# mega-breakout-v1.net
KiCad netlist of a schematic drawn in EAGLE
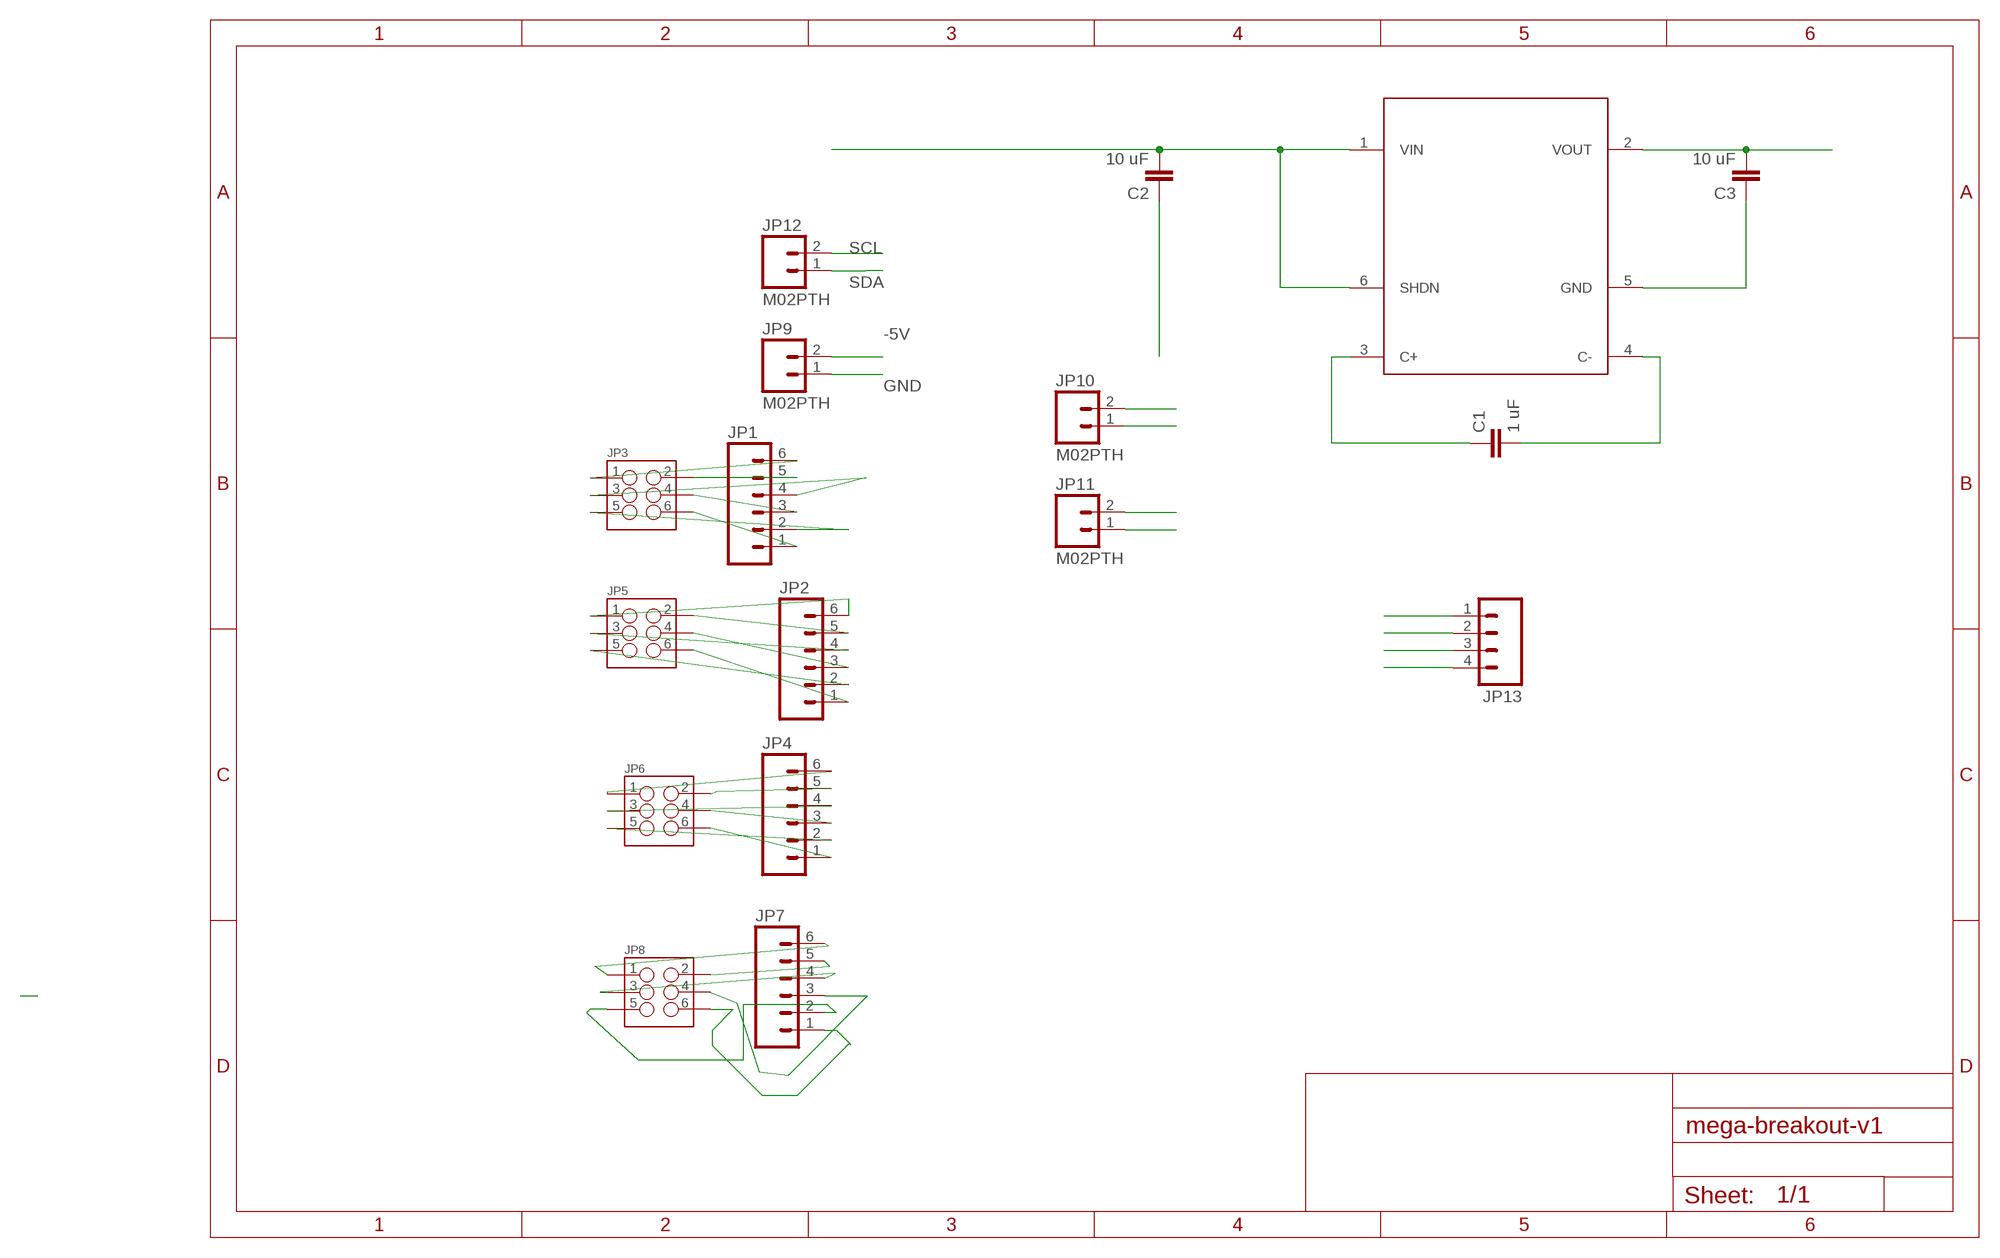
[diagram p0: schematic, sheet 1]

(export (version "E")
  (design (tool "Eeschema 10.0.6"))
  (components
    (comp (ref "C1")
      (value "1 uF")
      (footprint "eagle-import:0805")
      (libsource (lib "eagle-import") (part "CAP0805"))
    )
    (comp (ref "C2")
      (value "10 uF")
      (footprint "eagle-import:0805")
      (libsource (lib "eagle-import") (part "CAP0805"))
    )
    (comp (ref "C3")
      (value "10 uF")
      (footprint "eagle-import:0805")
      (libsource (lib "eagle-import") (part "CAP0805"))
    )
    (comp (ref "JP1")
      (value "M06NO_SILK")
      (footprint "eagle-import:1X06_NO_SILK")
      (libsource (lib "eagle-import") (part "M06NO_SILK"))
    )
    (comp (ref "JP2")
      (value "M06NO_SILK")
      (footprint "eagle-import:1X06_NO_SILK")
      (libsource (lib "eagle-import") (part "M06NO_SILK"))
    )
    (comp (ref "JP3")
      (value "M03X22X3_SILK_SM")
      (footprint "eagle-import:2X3")
      (libsource (lib "eagle-import") (part "M03X22X3_SILK_SM"))
    )
    (comp (ref "JP4")
      (value "M06NO_SILK")
      (footprint "eagle-import:1X06_NO_SILK")
      (libsource (lib "eagle-import") (part "M06NO_SILK"))
    )
    (comp (ref "JP5")
      (value "M03X22X3_SILK_SM")
      (footprint "eagle-import:2X3")
      (libsource (lib "eagle-import") (part "M03X22X3_SILK_SM"))
    )
    (comp (ref "JP6")
      (value "M03X22X3_SILK_SM")
      (footprint "eagle-import:2X3")
      (libsource (lib "eagle-import") (part "M03X22X3_SILK_SM"))
    )
    (comp (ref "JP7")
      (value "M06NO_SILK")
      (footprint "eagle-import:1X06_NO_SILK")
      (libsource (lib "eagle-import") (part "M06NO_SILK"))
    )
    (comp (ref "JP8")
      (value "M03X22X3_SILK_SM")
      (footprint "eagle-import:2X3")
      (libsource (lib "eagle-import") (part "M03X22X3_SILK_SM"))
    )
    (comp (ref "JP9")
      (value "M02PTH")
      (footprint "eagle-import:1X02")
      (libsource (lib "eagle-import") (part "M02PTH"))
    )
    (comp (ref "JP10")
      (value "M02PTH")
      (footprint "eagle-import:1X02")
      (libsource (lib "eagle-import") (part "M02PTH"))
    )
    (comp (ref "JP11")
      (value "M02PTH")
      (footprint "eagle-import:1X02")
      (libsource (lib "eagle-import") (part "M02PTH"))
    )
    (comp (ref "JP12")
      (value "M02PTH")
      (footprint "eagle-import:1X02")
      (libsource (lib "eagle-import") (part "M02PTH"))
    )
    (comp (ref "JP13")
      (value "M04PTH")
      (footprint "eagle-import:1X04")
      (libsource (lib "eagle-import") (part "M04PTH"))
    )
    (comp (ref "U1")
      (value "LTC1983")
      (footprint "eagle-import:SSOT23-6")
      (libsource (lib "eagle-import") (part "LTC1983"))
    )
  )
  (nets
    (net (code "1") (name "/-5V") (class "Default")
      (node (ref "C3") (pin "2") (pinfunction "2_2") (pintype "passive"))
      (node (ref "JP9") (pin "2") (pinfunction "2_2") (pintype "passive"))
      (node (ref "U1") (pin "2") (pinfunction "VOUT_2") (pintype "bidirectional"))
    )
    (net (code "2") (name "/GND") (class "Default")
      (node (ref "JP13") (pin "3") (pinfunction "3_3") (pintype "passive"))
      (node (ref "JP9") (pin "1") (pinfunction "1_1") (pintype "passive"))
    )
    (net (code "3") (name "/SCL") (class "Default")
      (node (ref "JP12") (pin "2") (pinfunction "2_2") (pintype "passive"))
      (node (ref "JP13") (pin "2") (pinfunction "2_2") (pintype "passive"))
    )
    (net (code "4") (name "/SDA") (class "Default")
      (node (ref "JP12") (pin "1") (pinfunction "1_1") (pintype "passive"))
      (node (ref "JP13") (pin "1") (pinfunction "1_1") (pintype "passive"))
    )
    (net (code "5") (name "/VCC") (class "Default")
      (node (ref "C2") (pin "2") (pinfunction "2_2") (pintype "passive"))
      (node (ref "JP11") (pin "1") (pinfunction "1_1") (pintype "passive"))
      (node (ref "JP11") (pin "2") (pinfunction "2_2") (pintype "passive"))
      (node (ref "JP13") (pin "4") (pinfunction "4_4") (pintype "passive"))
      (node (ref "U1") (pin "1") (pinfunction "VIN_1") (pintype "bidirectional"))
      (node (ref "U1") (pin "6") (pinfunction "SHDN_6") (pintype "bidirectional"))
    )
    (net (code "6") (name "/VCC1") (class "Default")
      (node (ref "C2") (pin "1") (pinfunction "1_1") (pintype "passive"))
      (node (ref "C3") (pin "1") (pinfunction "1_1") (pintype "passive"))
      (node (ref "U1") (pin "5") (pinfunction "GND_5") (pintype "bidirectional"))
    )
    (net (code "7") (name "Net-(JP1-Pad1)") (class "Default")
      (node (ref "JP1") (pin "1") (pinfunction "1_1") (pintype "passive"))
      (node (ref "JP3") (pin "6") (pinfunction "6_6") (pintype "bidirectional"))
    )
    (net (code "8") (name "Net-(JP1-Pad2)") (class "Default")
      (node (ref "JP1") (pin "2") (pinfunction "2_2") (pintype "passive"))
      (node (ref "JP3") (pin "5") (pinfunction "5_5") (pintype "bidirectional"))
    )
    (net (code "9") (name "Net-(JP1-Pad3)") (class "Default")
      (node (ref "JP1") (pin "3") (pinfunction "3_3") (pintype "passive"))
      (node (ref "JP3") (pin "4") (pinfunction "4_4") (pintype "bidirectional"))
    )
    (net (code "10") (name "Net-(JP1-Pad4)") (class "Default")
      (node (ref "JP1") (pin "4") (pinfunction "4_4") (pintype "passive"))
      (node (ref "JP3") (pin "3") (pinfunction "3_3") (pintype "bidirectional"))
    )
    (net (code "11") (name "Net-(JP1-Pad5)") (class "Default")
      (node (ref "JP1") (pin "5") (pinfunction "5_5") (pintype "passive"))
      (node (ref "JP3") (pin "2") (pinfunction "2_2") (pintype "bidirectional"))
    )
    (net (code "12") (name "Net-(JP1-Pad6)") (class "Default")
      (node (ref "JP1") (pin "6") (pinfunction "6_6") (pintype "passive"))
      (node (ref "JP3") (pin "1") (pinfunction "1_1") (pintype "bidirectional"))
    )
    (net (code "13") (name "Net-(JP2-Pad1)") (class "Default")
      (node (ref "JP2") (pin "1") (pinfunction "1_1") (pintype "passive"))
      (node (ref "JP5") (pin "6") (pinfunction "6_6") (pintype "bidirectional"))
    )
    (net (code "14") (name "Net-(JP2-Pad2)") (class "Default")
      (node (ref "JP2") (pin "2") (pinfunction "2_2") (pintype "passive"))
      (node (ref "JP5") (pin "5") (pinfunction "5_5") (pintype "bidirectional"))
    )
    (net (code "15") (name "Net-(JP2-Pad3)") (class "Default")
      (node (ref "JP2") (pin "3") (pinfunction "3_3") (pintype "passive"))
      (node (ref "JP5") (pin "4") (pinfunction "4_4") (pintype "bidirectional"))
    )
    (net (code "16") (name "Net-(JP2-Pad4)") (class "Default")
      (node (ref "JP2") (pin "4") (pinfunction "4_4") (pintype "passive"))
      (node (ref "JP5") (pin "3") (pinfunction "3_3") (pintype "bidirectional"))
    )
    (net (code "17") (name "Net-(JP2-Pad5)") (class "Default")
      (node (ref "JP2") (pin "5") (pinfunction "5_5") (pintype "passive"))
      (node (ref "JP5") (pin "2") (pinfunction "2_2") (pintype "bidirectional"))
    )
    (net (code "18") (name "Net-(JP2-Pad6)") (class "Default")
      (node (ref "JP2") (pin "6") (pinfunction "6_6") (pintype "passive"))
      (node (ref "JP5") (pin "1") (pinfunction "1_1") (pintype "bidirectional"))
    )
    (net (code "19") (name "Net-(JP4-Pad1)") (class "Default")
      (node (ref "JP4") (pin "1") (pinfunction "1_1") (pintype "passive"))
      (node (ref "JP6") (pin "6") (pinfunction "6_6") (pintype "bidirectional"))
    )
    (net (code "20") (name "Net-(JP4-Pad2)") (class "Default")
      (node (ref "JP4") (pin "2") (pinfunction "2_2") (pintype "passive"))
      (node (ref "JP6") (pin "5") (pinfunction "5_5") (pintype "bidirectional"))
    )
    (net (code "21") (name "Net-(JP4-Pad3)") (class "Default")
      (node (ref "JP4") (pin "3") (pinfunction "3_3") (pintype "passive"))
      (node (ref "JP6") (pin "4") (pinfunction "4_4") (pintype "bidirectional"))
    )
    (net (code "22") (name "Net-(JP4-Pad4)") (class "Default")
      (node (ref "JP4") (pin "4") (pinfunction "4_4") (pintype "passive"))
      (node (ref "JP6") (pin "3") (pinfunction "3_3") (pintype "bidirectional"))
    )
    (net (code "23") (name "Net-(JP4-Pad5)") (class "Default")
      (node (ref "JP4") (pin "5") (pinfunction "5_5") (pintype "passive"))
      (node (ref "JP6") (pin "2") (pinfunction "2_2") (pintype "bidirectional"))
    )
    (net (code "24") (name "Net-(JP4-Pad6)") (class "Default")
      (node (ref "JP4") (pin "6") (pinfunction "6_6") (pintype "passive"))
      (node (ref "JP6") (pin "1") (pinfunction "1_1") (pintype "bidirectional"))
    )
    (net (code "25") (name "Net-(JP7-Pad1)") (class "Default")
      (node (ref "JP7") (pin "1") (pinfunction "1_1") (pintype "passive"))
      (node (ref "JP8") (pin "6") (pinfunction "6_6") (pintype "bidirectional"))
    )
    (net (code "26") (name "Net-(JP7-Pad2)") (class "Default")
      (node (ref "JP7") (pin "2") (pinfunction "2_2") (pintype "passive"))
      (node (ref "JP8") (pin "5") (pinfunction "5_5") (pintype "bidirectional"))
    )
    (net (code "27") (name "Net-(JP7-Pad3)") (class "Default")
      (node (ref "JP7") (pin "3") (pinfunction "3_3") (pintype "passive"))
      (node (ref "JP8") (pin "4") (pinfunction "4_4") (pintype "bidirectional"))
    )
    (net (code "28") (name "Net-(JP7-Pad4)") (class "Default")
      (node (ref "JP7") (pin "4") (pinfunction "4_4") (pintype "passive"))
      (node (ref "JP8") (pin "3") (pinfunction "3_3") (pintype "bidirectional"))
    )
    (net (code "29") (name "Net-(JP7-Pad5)") (class "Default")
      (node (ref "JP7") (pin "5") (pinfunction "5_5") (pintype "passive"))
      (node (ref "JP8") (pin "2") (pinfunction "2_2") (pintype "bidirectional"))
    )
    (net (code "30") (name "Net-(JP7-Pad6)") (class "Default")
      (node (ref "JP7") (pin "6") (pinfunction "6_6") (pintype "passive"))
      (node (ref "JP8") (pin "1") (pinfunction "1_1") (pintype "bidirectional"))
    )
    (net (code "31") (name "Net-(U1-C+)") (class "Default")
      (node (ref "C1") (pin "1") (pinfunction "1_1") (pintype "passive"))
      (node (ref "U1") (pin "3") (pinfunction "C+_3") (pintype "bidirectional"))
    )
    (net (code "32") (name "Net-(U1-C-)") (class "Default")
      (node (ref "C1") (pin "2") (pinfunction "2_2") (pintype "passive"))
      (node (ref "U1") (pin "4") (pinfunction "C-_4") (pintype "bidirectional"))
    )
    (net (code "33") (name "unconnected-(JP10-Pad1)") (class "Default")
      (node (ref "JP10") (pin "1") (pinfunction "1_1") (pintype "passive"))
    )
    (net (code "34") (name "unconnected-(JP10-Pad2)") (class "Default")
      (node (ref "JP10") (pin "2") (pinfunction "2_2") (pintype "passive"))
    )
  )
)
